# USF-IEEE-CS.net
KiCad netlist of a schematic drawn in Altium Designer
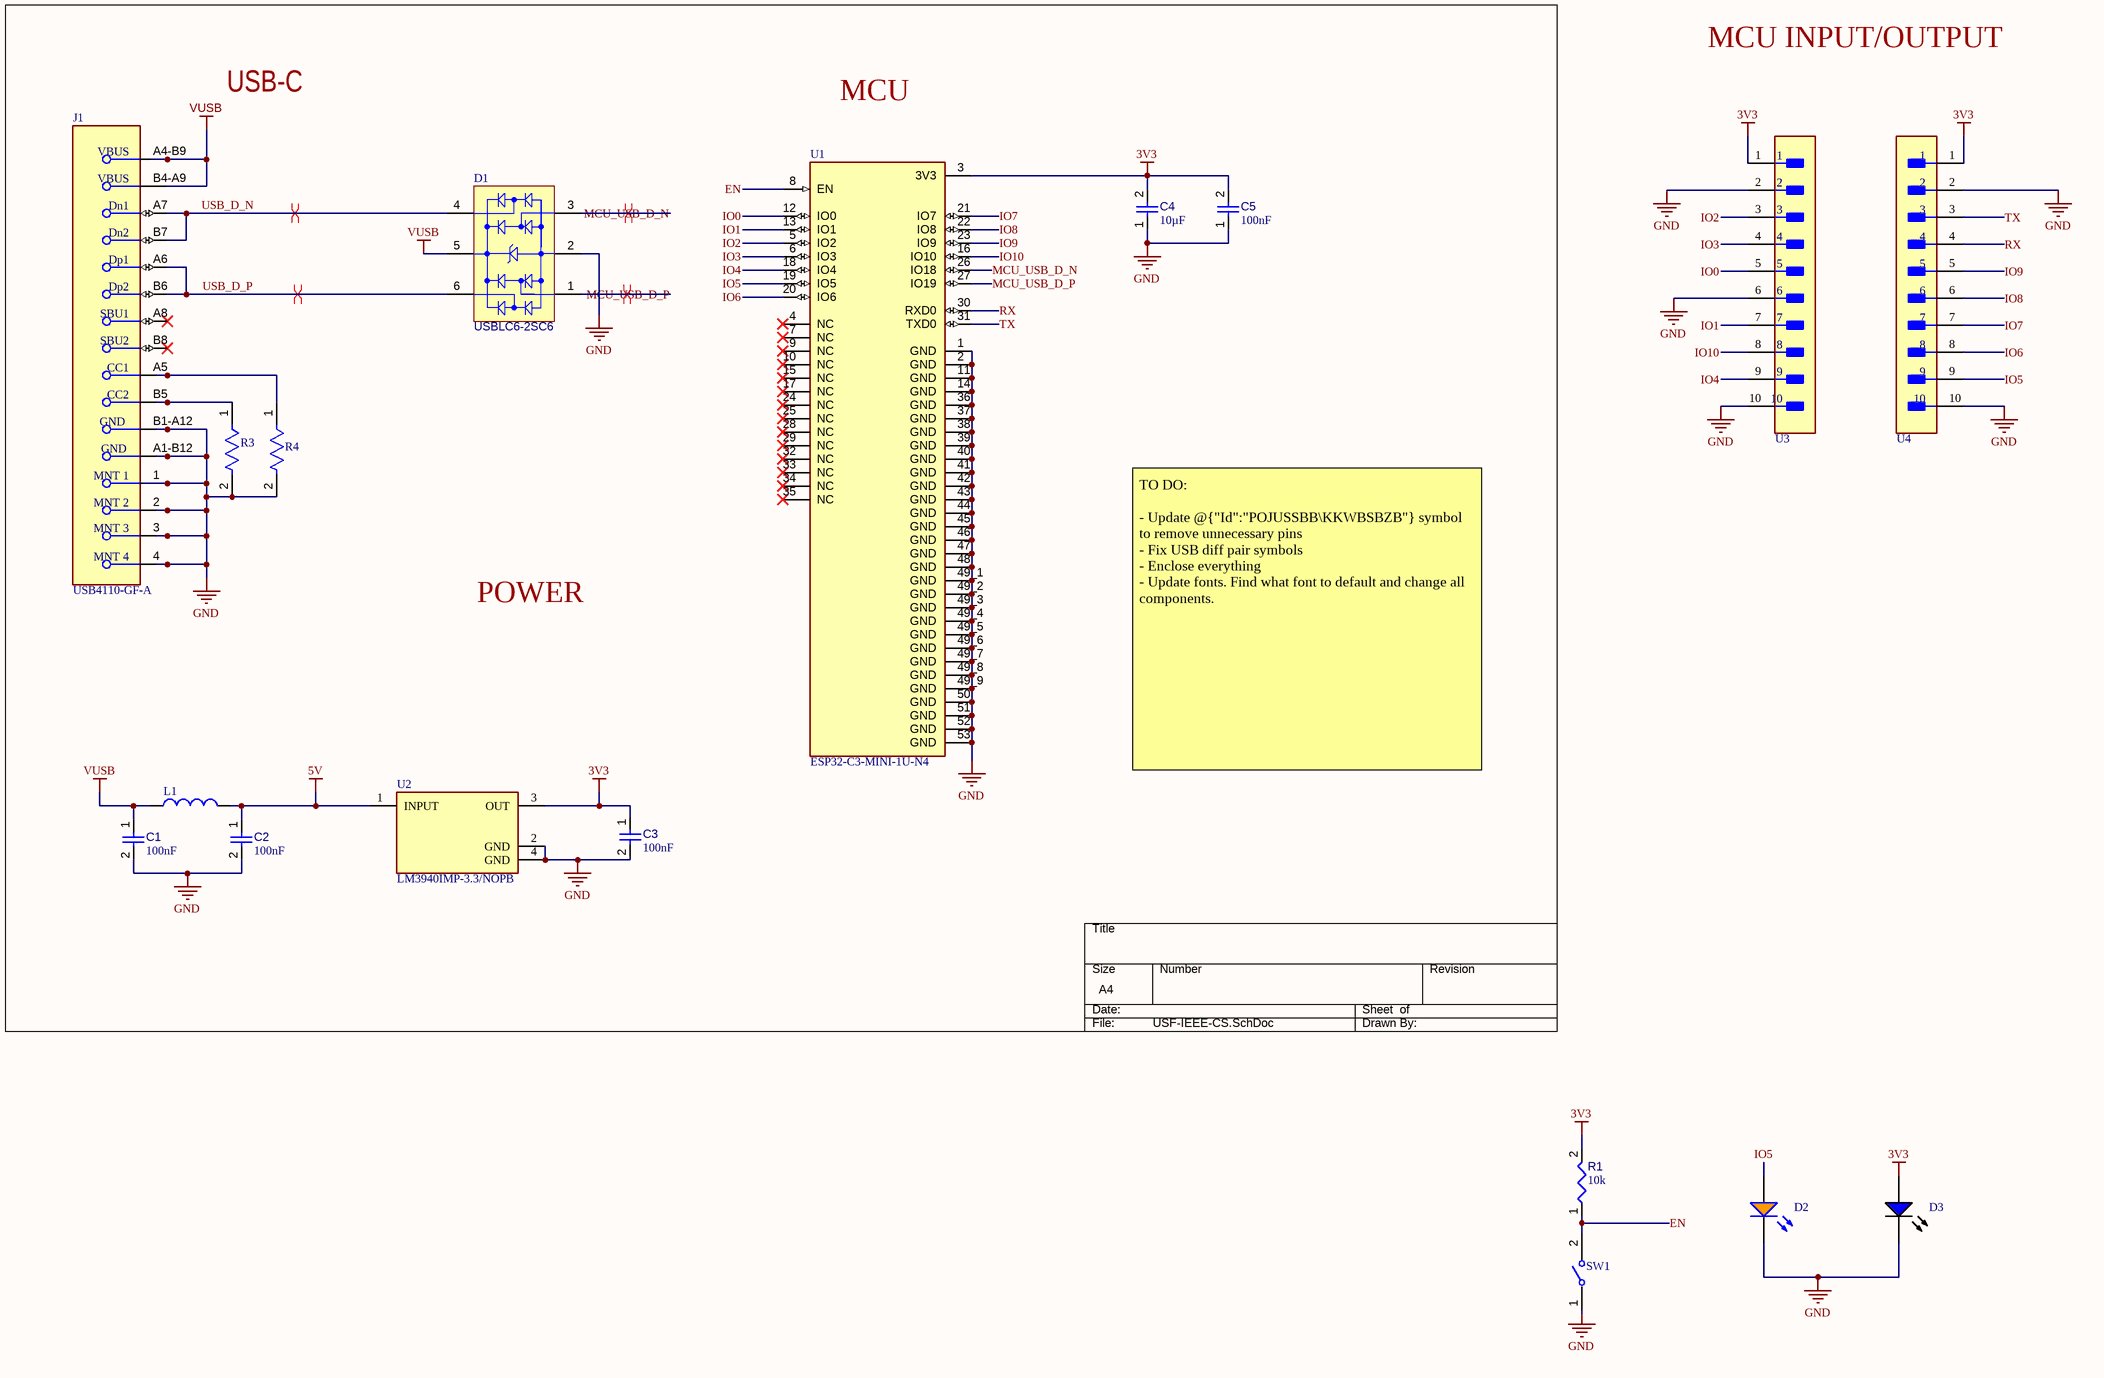
[diagram p0: USF-IEEE-CS.SchDoc]

(export (version "E")
  (design (tool "Eeschema 10.0.6"))
  (components
    (comp (ref "C1")
      (value "100nF")
      (footprint "CAPC1608X90X40NL10T20")
      (description "Chip Capacitor, 100 nF, +/- 10%, 50 V, 0603 (1608 Metric)")
      (fields (field (name "TOLERANCE") "10%") (field (name "Comment") "Capacitor 100 nF +/-10% 50 V 0603"))
      (libsource (lib "University of South Florida") (part "CAP-NP-2"))
    )
    (comp (ref "C2")
      (value "100nF")
      (footprint "CAPC1608X90X40NL10T20")
      (description "Chip Capacitor, 100 nF, +/- 10%, 50 V, 0603 (1608 Metric)")
      (fields (field (name "TOLERANCE") "10%") (field (name "Comment") "Capacitor 100 nF +/-10% 50 V 0603"))
      (libsource (lib "University of South Florida") (part "CAP-NP-2"))
    )
    (comp (ref "C3")
      (value "100nF")
      (footprint "CAPC1608X90X40NL10T20")
      (description "Chip Capacitor, 100 nF, +/- 10%, 50 V, 0603 (1608 Metric)")
      (fields (field (name "TOLERANCE") "10%") (field (name "Comment") "Capacitor 100 nF +/-10% 50 V 0603"))
      (libsource (lib "University of South Florida") (part "CAP-NP-2"))
    )
    (comp (ref "C4")
      (value "10µF")
      (footprint "CAPC0603(1608)100_L")
      (description "Chip Capacitor, 10µF +/-20%, 10V, 0603, Thickness 1 mm")
      (fields (field (name "TOLERANCE") "10%") (field (name "Comment") "Capacitor 10µF +/-20% 10V 0603"))
      (libsource (lib "University of South Florida") (part "CAP-NP-2"))
    )
    (comp (ref "C5")
      (value "100nF")
      (footprint "CAPC1608X90X40NL10T20")
      (description "Chip Capacitor, 100 nF, +/- 10%, 50 V, 0603 (1608 Metric)")
      (fields (field (name "TOLERANCE") "10%") (field (name "Comment") "Capacitor 100 nF +/-10% 50 V 0603"))
      (libsource (lib "University of South Florida") (part "CAP-NP-2"))
    )
    (comp (ref "D1")
      (value "USBLC6-2SC6")
      (footprint "STM-SOT23-6L_V")
      (description "Very low capacitance ESD protection, 3.5 pF, -40 to 125 degC, 6-Pin SOT23, RoHS, Tape and Reel")
      (fields (field (name "MANUFACTURER") "STMicroelectronics"))
      (libsource (lib "Altium Content Vault") (part "STM-USB_DVI_HDMIULC6-4SC6X-SOT23-6L"))
    )
    (comp (ref "D2")
      (value "LTST-C190AKT")
      (footprint "LTST-C190AKT-2_V")
      (description "LED Uni-Color Orange, 100 mW, 30 mA, -55 to 85 degC, 2-Pin SMD, RoHS, Tape and Reel")
      (fields (field (name "MANUFACTURER") "Lite-On"))
      (libsource (lib "University of South Florida") (part "LED-ORANGE-AK-2"))
    )
    (comp (ref "D3")
      (value "LTST-C190TBKT")
      (footprint "LTST-C190TBKT-2_V")
      (description "LED Uni-Color Blue, 76 mW, 20 mA, -20 to 80 degC, 2-Pin SMD, RoHS, Tape and Reel")
      (fields (field (name "MANUFACTURER") "Lite-On"))
      (libsource (lib "University of South Florida") (part "LED-BLUE-AK-2"))
    )
    (comp (ref "J1")
      (value "USB4110-GF-A")
      (footprint "FP-USB4110-GF-A-MFG")
      (description "Conn USB Type C RCP 16 POS 0.3mm/0.5mm Solder ST SMD 16 Terminal 1 Port T/R")
      (libsource (lib "University of South Florida") (part "e23f2b38bb3c3f98e683ebab9ede730"))
    )
    (comp (ref "L1")
      (value "LQG18HN2N2S00D")
      (footprint "FP-LQG18HH_00-IPC_A")
      (description "General Purpose Inductor, 0.0022uH, 13.636%, 1 Element, Air-Core, SMD, 0603")
      (fields (field (name "TOLERANCE") "13.636%"))
      (libsource (lib "University of South Florida") (part "IND-2"))
    )
    (comp (ref "R1")
      (value "10k")
      (footprint "RESC1608X55X25ML10T15")
      (description "Chip Resistor, 10 KOhm, +/- 1%, 01 W, -55 to 155 degC, 0603 (1608 Metric)")
      (fields (field (name "POWER") "100mW") (field (name "TOLERANCE") "1%"))
      (libsource (lib "University of South Florida") (part "RES-2"))
    )
    (comp (ref "R3")
      (value "ERA-3AEB512V")
      (footprint "FP-ERA3A-MFG")
      (description "Res Thin Film 0603 5.1K Ohm 0.1% 1/10W ±25ppm/°C Molded SMD SMD Punched Carrier T/R")
      (libsource (lib "University of South Florida") (part "8db39607336c341a927600551d01821"))
    )
    (comp (ref "R4")
      (value "ERA-3AEB512V")
      (footprint "FP-ERA3A-MFG")
      (description "Res Thin Film 0603 5.1K Ohm 0.1% 1/10W ±25ppm/°C Molded SMD SMD Punched Carrier T/R")
      (libsource (lib "University of South Florida") (part "8db39607336c341a927600551d01821"))
    )
    (comp (ref "SW1")
      (value "B3U-1000P")
      (footprint "FP-B3U-1000P-MFG")
      (description "SWITCH TACTILE SPST-NO 0.05A 12V")
      (libsource (lib "Altium Content Vault") (part "ae622034201233ca1abcedc05908f33"))
    )
    (comp (ref "U1")
      (value "ESP32-C3-MINI-1U-N4")
      (footprint "XCVR_ESP32-C3-MINI-1U-N4")
      (fields (field (name "MF") "Espressif Systems"))
      (libsource (lib "University of South Florida") (part "ESP32-C3-MINI-1U-N4"))
    )
    (comp (ref "U2")
      (value "LM3940IMP-3.3/NOPB")
      (footprint "FP-DCY0004A-IPC_C")
      (description "IC REG LDO 3.3V 1A SOT223")
      (libsource (lib "University of South Florida") (part "ef78896361455d16e3252a05c23564e"))
    )
    (comp (ref "U3")
      (value "61301011121")
      (footprint "FP-61301011121-MFG")
      (libsource (lib "University of South Florida") (part "aee40dc8b284c03a16094555aa210be"))
    )
    (comp (ref "U4")
      (value "61301011121")
      (footprint "FP-61301011121-MFG")
      (libsource (lib "") (part "aee40dc8b284c03a16094555aa210be_1"))
    )
  )
  (nets
    (net (code "1") (name "/EN") (class "Default")
      (node (ref "R1") (pin "1") (pinfunction "1_1") (pintype "passive"))
      (node (ref "SW1") (pin "2") (pinfunction "2_2") (pintype "passive"))
      (node (ref "U1") (pin "8") (pinfunction "EN_8") (pintype "input"))
    )
    (net (code "2") (name "/IO0") (class "Default")
      (node (ref "U1") (pin "12") (pinfunction "IO0_12") (pintype "bidirectional"))
      (node (ref "U3") (pin "5") (pinfunction "5_5") (pintype "passive"))
    )
    (net (code "3") (name "/IO1") (class "Default")
      (node (ref "U1") (pin "13") (pinfunction "IO1_13") (pintype "bidirectional"))
      (node (ref "U3") (pin "7") (pinfunction "7_7") (pintype "passive"))
    )
    (net (code "4") (name "/IO2") (class "Default")
      (node (ref "U1") (pin "5") (pinfunction "IO2_5") (pintype "bidirectional"))
      (node (ref "U3") (pin "3") (pinfunction "3_3") (pintype "passive"))
    )
    (net (code "5") (name "/IO3") (class "Default")
      (node (ref "U1") (pin "6") (pinfunction "IO3_6") (pintype "bidirectional"))
      (node (ref "U3") (pin "4") (pinfunction "4_4") (pintype "passive"))
    )
    (net (code "6") (name "/IO4") (class "Default")
      (node (ref "U1") (pin "18") (pinfunction "IO4_18") (pintype "bidirectional"))
      (node (ref "U3") (pin "9") (pinfunction "9_9") (pintype "passive"))
    )
    (net (code "7") (name "/IO5") (class "Default")
      (node (ref "D2") (pin "1") (pinfunction "A_1") (pintype "passive"))
      (node (ref "U1") (pin "19") (pinfunction "IO5_19") (pintype "bidirectional"))
      (node (ref "U4") (pin "9") (pinfunction "9_9") (pintype "passive"))
    )
    (net (code "8") (name "/IO6") (class "Default")
      (node (ref "U1") (pin "20") (pinfunction "IO6_20") (pintype "bidirectional"))
      (node (ref "U4") (pin "8") (pinfunction "8_8") (pintype "passive"))
    )
    (net (code "9") (name "/IO7") (class "Default")
      (node (ref "U1") (pin "21") (pinfunction "IO7_21") (pintype "bidirectional"))
      (node (ref "U4") (pin "7") (pinfunction "7_7") (pintype "passive"))
    )
    (net (code "10") (name "/IO8") (class "Default")
      (node (ref "U1") (pin "22") (pinfunction "IO8_22") (pintype "bidirectional"))
      (node (ref "U4") (pin "6") (pinfunction "6_6") (pintype "passive"))
    )
    (net (code "11") (name "/IO9") (class "Default")
      (node (ref "U1") (pin "23") (pinfunction "IO9_23") (pintype "bidirectional"))
      (node (ref "U4") (pin "5") (pinfunction "5_5") (pintype "passive"))
    )
    (net (code "12") (name "/IO10") (class "Default")
      (node (ref "U1") (pin "16") (pinfunction "IO10_16") (pintype "bidirectional"))
      (node (ref "U3") (pin "8") (pinfunction "8_8") (pintype "passive"))
    )
    (net (code "13") (name "/MCU_USB_D_N") (class "Default")
      (node (ref "D1") (pin "3") (pinfunction "I/O_2_3") (pintype "passive"))
      (node (ref "U1") (pin "26") (pinfunction "IO18_26") (pintype "bidirectional"))
    )
    (net (code "14") (name "/MCU_USB_D_P") (class "Default")
      (node (ref "D1") (pin "1") (pinfunction "I/O_1_1") (pintype "passive"))
      (node (ref "U1") (pin "27") (pinfunction "IO19_27") (pintype "bidirectional"))
    )
    (net (code "15") (name "/RX") (class "Default")
      (node (ref "U1") (pin "30") (pinfunction "RXD0_30") (pintype "bidirectional"))
      (node (ref "U4") (pin "4") (pinfunction "4_4") (pintype "passive"))
    )
    (net (code "16") (name "/TX") (class "Default")
      (node (ref "U1") (pin "31") (pinfunction "TXD0_31") (pintype "bidirectional"))
      (node (ref "U4") (pin "3") (pinfunction "3_3") (pintype "passive"))
    )
    (net (code "17") (name "/USB_D_N") (class "Default")
      (node (ref "D1") (pin "4") (pinfunction "I/O_3_4") (pintype "passive"))
      (node (ref "J1") (pin "A7") (pinfunction "Dn1_A7") (pintype "bidirectional"))
      (node (ref "J1") (pin "B7") (pinfunction "Dn2_B7") (pintype "bidirectional"))
    )
    (net (code "18") (name "/USB_D_P") (class "Default")
      (node (ref "D1") (pin "6") (pinfunction "I/O_4_6") (pintype "passive"))
      (node (ref "J1") (pin "A6") (pinfunction "Dp1_A6") (pintype "bidirectional"))
      (node (ref "J1") (pin "B6") (pinfunction "Dp2_B6") (pintype "bidirectional"))
    )
    (net (code "19") (name "3V3") (class "Default")
      (node (ref "C3") (pin "1") (pinfunction "1_1") (pintype "passive"))
      (node (ref "C4") (pin "2") (pinfunction "2_2") (pintype "passive"))
      (node (ref "C5") (pin "2") (pinfunction "2_2") (pintype "passive"))
      (node (ref "D3") (pin "1") (pinfunction "A_1") (pintype "passive"))
      (node (ref "R1") (pin "2") (pinfunction "2_2") (pintype "passive"))
      (node (ref "U1") (pin "3") (pinfunction "3V3_3") (pintype "power_in"))
      (node (ref "U2") (pin "3") (pinfunction "OUT_3") (pintype "power_in"))
      (node (ref "U3") (pin "1") (pinfunction "1_1") (pintype "passive"))
      (node (ref "U4") (pin "1") (pinfunction "1_1") (pintype "passive"))
    )
    (net (code "20") (name "5V") (class "Default")
      (node (ref "C2") (pin "1") (pinfunction "1_1") (pintype "passive"))
      (node (ref "L1") (pin "2") (pinfunction "2_2") (pintype "passive"))
      (node (ref "U2") (pin "1") (pinfunction "INPUT_1") (pintype "power_in"))
    )
    (net (code "21") (name "GND") (class "Default")
      (node (ref "C1") (pin "2") (pinfunction "2_2") (pintype "passive"))
      (node (ref "C2") (pin "2") (pinfunction "2_2") (pintype "passive"))
      (node (ref "C3") (pin "2") (pinfunction "2_2") (pintype "passive"))
      (node (ref "C4") (pin "1") (pinfunction "1_1") (pintype "passive"))
      (node (ref "C5") (pin "1") (pinfunction "1_1") (pintype "passive"))
      (node (ref "D1") (pin "2") (pinfunction "GND_2") (pintype "passive"))
      (node (ref "D2") (pin "2") (pinfunction "K_2") (pintype "passive"))
      (node (ref "D3") (pin "2") (pinfunction "K_2") (pintype "passive"))
      (node (ref "J1") (pin "1") (pinfunction "MNT_1_1") (pintype "passive"))
      (node (ref "J1") (pin "2") (pinfunction "MNT_2_2") (pintype "passive"))
      (node (ref "J1") (pin "3") (pinfunction "MNT_3_3") (pintype "passive"))
      (node (ref "J1") (pin "4") (pinfunction "MNT_4_4") (pintype "passive"))
      (node (ref "J1") (pin "A1-B12") (pinfunction "GND_A1-B12") (pintype "passive"))
      (node (ref "J1") (pin "B1-A12") (pinfunction "GND_B1-A12") (pintype "passive"))
      (node (ref "R3") (pin "2") (pinfunction "2_2") (pintype "passive"))
      (node (ref "R4") (pin "2") (pinfunction "2_2") (pintype "passive"))
      (node (ref "SW1") (pin "1") (pinfunction "1_1") (pintype "passive"))
      (node (ref "U1") (pin "1") (pinfunction "GND_1") (pintype "power_in"))
      (node (ref "U1") (pin "11") (pinfunction "GND_11") (pintype "power_in"))
      (node (ref "U1") (pin "14") (pinfunction "GND_14") (pintype "power_in"))
      (node (ref "U1") (pin "2") (pinfunction "GND_2") (pintype "power_in"))
      (node (ref "U1") (pin "36") (pinfunction "GND_36") (pintype "power_in"))
      (node (ref "U1") (pin "37") (pinfunction "GND_37") (pintype "power_in"))
      (node (ref "U1") (pin "38") (pinfunction "GND_38") (pintype "power_in"))
      (node (ref "U1") (pin "39") (pinfunction "GND_39") (pintype "power_in"))
      (node (ref "U1") (pin "40") (pinfunction "GND_40") (pintype "power_in"))
      (node (ref "U1") (pin "41") (pinfunction "GND_41") (pintype "power_in"))
      (node (ref "U1") (pin "42") (pinfunction "GND_42") (pintype "power_in"))
      (node (ref "U1") (pin "43") (pinfunction "GND_43") (pintype "power_in"))
      (node (ref "U1") (pin "44") (pinfunction "GND_44") (pintype "power_in"))
      (node (ref "U1") (pin "45") (pinfunction "GND_45") (pintype "power_in"))
      (node (ref "U1") (pin "46") (pinfunction "GND_46") (pintype "power_in"))
      (node (ref "U1") (pin "47") (pinfunction "GND_47") (pintype "power_in"))
      (node (ref "U1") (pin "48") (pinfunction "GND_48") (pintype "power_in"))
      (node (ref "U1") (pin "49_1") (pinfunction "GND_49_1") (pintype "power_in"))
      (node (ref "U1") (pin "49_2") (pinfunction "GND_49_2") (pintype "power_in"))
      (node (ref "U1") (pin "49_3") (pinfunction "GND_49_3") (pintype "power_in"))
      (node (ref "U1") (pin "49_4") (pinfunction "GND_49_4") (pintype "power_in"))
      (node (ref "U1") (pin "49_5") (pinfunction "GND_49_5") (pintype "power_in"))
      (node (ref "U1") (pin "49_6") (pinfunction "GND_49_6") (pintype "power_in"))
      (node (ref "U1") (pin "49_7") (pinfunction "GND_49_7") (pintype "power_in"))
      (node (ref "U1") (pin "49_8") (pinfunction "GND_49_8") (pintype "power_in"))
      (node (ref "U1") (pin "49_9") (pinfunction "GND_49_9") (pintype "power_in"))
      (node (ref "U1") (pin "50") (pinfunction "GND_50") (pintype "power_in"))
      (node (ref "U1") (pin "51") (pinfunction "GND_51") (pintype "power_in"))
      (node (ref "U1") (pin "52") (pinfunction "GND_52") (pintype "power_in"))
      (node (ref "U1") (pin "53") (pinfunction "GND_53") (pintype "power_in"))
      (node (ref "U2") (pin "2") (pinfunction "GND_2") (pintype "power_in"))
      (node (ref "U2") (pin "4") (pinfunction "GND_4") (pintype "power_in"))
      (node (ref "U3") (pin "10") (pinfunction "10_10") (pintype "passive"))
      (node (ref "U3") (pin "2") (pinfunction "2_2") (pintype "passive"))
      (node (ref "U3") (pin "6") (pinfunction "6_6") (pintype "passive"))
      (node (ref "U4") (pin "10") (pinfunction "10_10") (pintype "passive"))
      (node (ref "U4") (pin "2") (pinfunction "2_2") (pintype "passive"))
    )
    (net (code "22") (name "Net-(J1-CC1)") (class "Default")
      (node (ref "J1") (pin "A5") (pinfunction "CC1_A5") (pintype "power_in"))
      (node (ref "R4") (pin "1") (pinfunction "1_1") (pintype "passive"))
    )
    (net (code "23") (name "Net-(J1-CC2)") (class "Default")
      (node (ref "J1") (pin "B5") (pinfunction "CC2_B5") (pintype "power_in"))
      (node (ref "R3") (pin "1") (pinfunction "1_1") (pintype "passive"))
    )
    (net (code "24") (name "VUSB") (class "Default")
      (node (ref "C1") (pin "1") (pinfunction "1_1") (pintype "passive"))
      (node (ref "D1") (pin "5") (pinfunction "VBUS_5") (pintype "passive"))
      (node (ref "J1") (pin "A4-B9") (pinfunction "VBUS_A4-B9") (pintype "power_in"))
      (node (ref "J1") (pin "B4-A9") (pinfunction "VBUS_B4-A9") (pintype "power_in"))
      (node (ref "L1") (pin "1") (pinfunction "1_1") (pintype "passive"))
    )
    (net (code "25") (name "unconnected-(J1-SBU1-PadA8)") (class "Default")
      (node (ref "J1") (pin "A8") (pinfunction "SBU1_A8") (pintype "bidirectional+no_connect"))
    )
    (net (code "26") (name "unconnected-(J1-SBU2-PadB8)") (class "Default")
      (node (ref "J1") (pin "B8") (pinfunction "SBU2_B8") (pintype "bidirectional+no_connect"))
    )
    (net (code "27") (name "unconnected-(U1-NC-Pad4)") (class "Default")
      (node (ref "U1") (pin "4") (pinfunction "NC_4") (pintype "passive+no_connect"))
    )
    (net (code "28") (name "unconnected-(U1-NC-Pad7)") (class "Default")
      (node (ref "U1") (pin "7") (pinfunction "NC_7") (pintype "passive+no_connect"))
    )
    (net (code "29") (name "unconnected-(U1-NC-Pad9)") (class "Default")
      (node (ref "U1") (pin "9") (pinfunction "NC_9") (pintype "passive+no_connect"))
    )
    (net (code "30") (name "unconnected-(U1-NC-Pad10)") (class "Default")
      (node (ref "U1") (pin "10") (pinfunction "NC_10") (pintype "passive+no_connect"))
    )
    (net (code "31") (name "unconnected-(U1-NC-Pad15)") (class "Default")
      (node (ref "U1") (pin "15") (pinfunction "NC_15") (pintype "passive+no_connect"))
    )
    (net (code "32") (name "unconnected-(U1-NC-Pad17)") (class "Default")
      (node (ref "U1") (pin "17") (pinfunction "NC_17") (pintype "passive+no_connect"))
    )
    (net (code "33") (name "unconnected-(U1-NC-Pad24)") (class "Default")
      (node (ref "U1") (pin "24") (pinfunction "NC_24") (pintype "passive+no_connect"))
    )
    (net (code "34") (name "unconnected-(U1-NC-Pad25)") (class "Default")
      (node (ref "U1") (pin "25") (pinfunction "NC_25") (pintype "passive+no_connect"))
    )
    (net (code "35") (name "unconnected-(U1-NC-Pad28)") (class "Default")
      (node (ref "U1") (pin "28") (pinfunction "NC_28") (pintype "passive+no_connect"))
    )
    (net (code "36") (name "unconnected-(U1-NC-Pad29)") (class "Default")
      (node (ref "U1") (pin "29") (pinfunction "NC_29") (pintype "passive+no_connect"))
    )
    (net (code "37") (name "unconnected-(U1-NC-Pad32)") (class "Default")
      (node (ref "U1") (pin "32") (pinfunction "NC_32") (pintype "passive+no_connect"))
    )
    (net (code "38") (name "unconnected-(U1-NC-Pad33)") (class "Default")
      (node (ref "U1") (pin "33") (pinfunction "NC_33") (pintype "passive+no_connect"))
    )
    (net (code "39") (name "unconnected-(U1-NC-Pad34)") (class "Default")
      (node (ref "U1") (pin "34") (pinfunction "NC_34") (pintype "passive+no_connect"))
    )
    (net (code "40") (name "unconnected-(U1-NC-Pad35)") (class "Default")
      (node (ref "U1") (pin "35") (pinfunction "NC_35") (pintype "passive+no_connect"))
    )
  )
)
